# XO-Tester.net
KiCad netlist of a schematic drawn in EAGLE
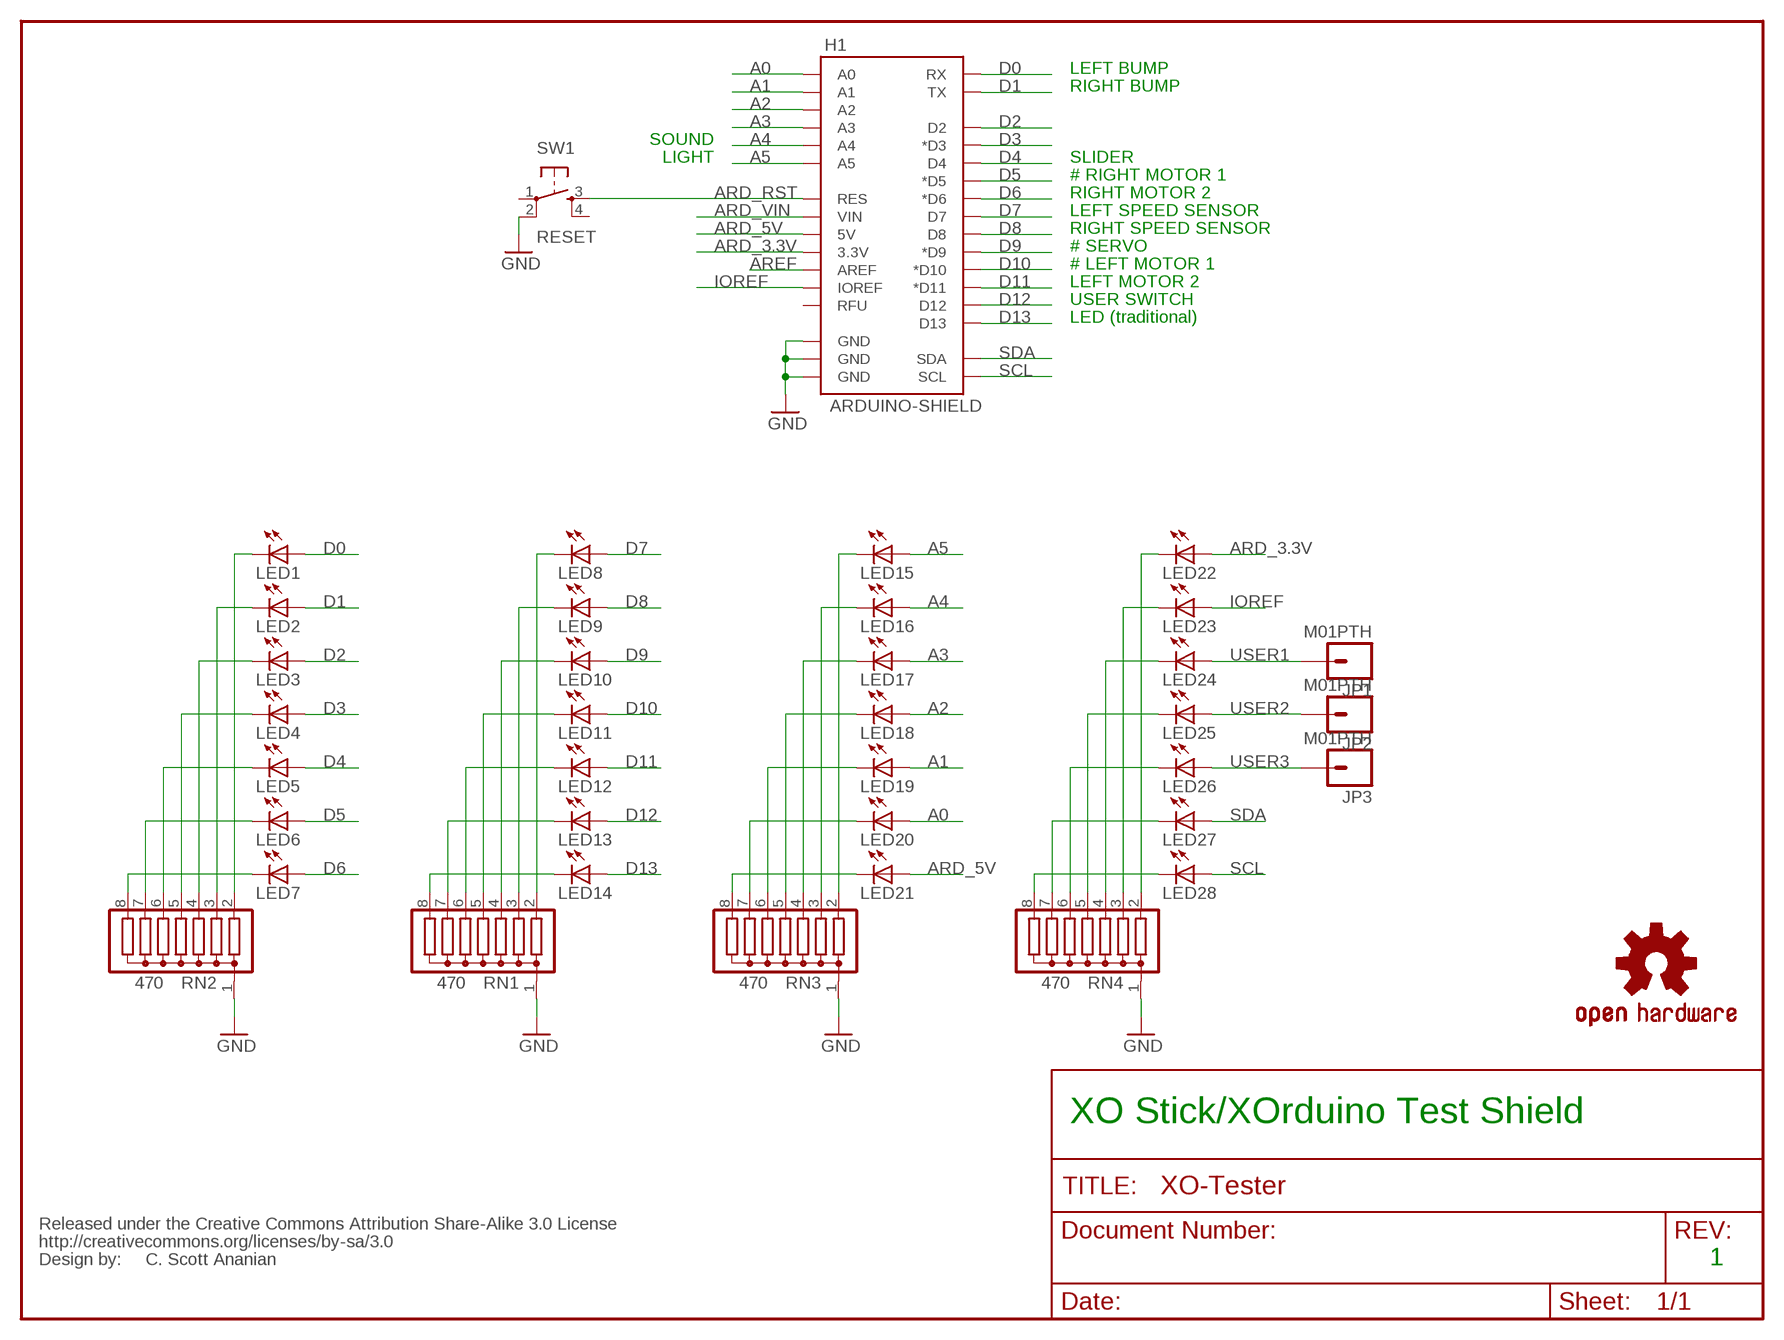
[diagram p0: schematic, sheet 1]

(export (version "E")
  (design (tool "Eeschema 10.0.6"))
  (components
    (comp (ref "H1")
      (value "ARDUINO-SHIELD")
      (footprint "eagle-import:ARDUINO-SHIELD-VIAS-HOLES")
      (libsource (lib "eagle-import") (part "ARDUINO-SHIELD"))
    )
    (comp (ref "JP1")
      (value "M01PTH")
      (footprint "eagle-import:1X01")
      (libsource (lib "eagle-import") (part "M01PTH"))
    )
    (comp (ref "JP2")
      (value "M01PTH")
      (footprint "eagle-import:1X01")
      (libsource (lib "eagle-import") (part "M01PTH"))
    )
    (comp (ref "JP3")
      (value "M01PTH")
      (footprint "eagle-import:1X01")
      (libsource (lib "eagle-import") (part "M01PTH"))
    )
    (comp (ref "LED1")
      (value "LED3MM-KIT")
      (footprint "eagle-import:LED3MM-KIT")
      (libsource (lib "eagle-import") (part "LED3MM-KIT"))
    )
    (comp (ref "LED2")
      (value "LED3MM-KIT")
      (footprint "eagle-import:LED3MM-KIT")
      (libsource (lib "eagle-import") (part "LED3MM-KIT"))
    )
    (comp (ref "LED3")
      (value "LED3MM-KIT")
      (footprint "eagle-import:LED3MM-KIT")
      (libsource (lib "eagle-import") (part "LED3MM-KIT"))
    )
    (comp (ref "LED4")
      (value "LED3MM-KIT")
      (footprint "eagle-import:LED3MM-KIT")
      (libsource (lib "eagle-import") (part "LED3MM-KIT"))
    )
    (comp (ref "LED5")
      (value "LED3MM-KIT")
      (footprint "eagle-import:LED3MM-KIT")
      (libsource (lib "eagle-import") (part "LED3MM-KIT"))
    )
    (comp (ref "LED6")
      (value "LED3MM-KIT")
      (footprint "eagle-import:LED3MM-KIT")
      (libsource (lib "eagle-import") (part "LED3MM-KIT"))
    )
    (comp (ref "LED7")
      (value "LED3MM-KIT")
      (footprint "eagle-import:LED3MM-KIT")
      (libsource (lib "eagle-import") (part "LED3MM-KIT"))
    )
    (comp (ref "LED8")
      (value "LED3MM-KIT")
      (footprint "eagle-import:LED3MM-KIT")
      (libsource (lib "eagle-import") (part "LED3MM-KIT"))
    )
    (comp (ref "LED9")
      (value "LED3MM-KIT")
      (footprint "eagle-import:LED3MM-KIT")
      (libsource (lib "eagle-import") (part "LED3MM-KIT"))
    )
    (comp (ref "LED10")
      (value "LED3MM-KIT")
      (footprint "eagle-import:LED3MM-KIT")
      (libsource (lib "eagle-import") (part "LED3MM-KIT"))
    )
    (comp (ref "LED11")
      (value "LED3MM-KIT")
      (footprint "eagle-import:LED3MM-KIT")
      (libsource (lib "eagle-import") (part "LED3MM-KIT"))
    )
    (comp (ref "LED12")
      (value "LED3MM-KIT")
      (footprint "eagle-import:LED3MM-KIT")
      (libsource (lib "eagle-import") (part "LED3MM-KIT"))
    )
    (comp (ref "LED13")
      (value "LED3MM-KIT")
      (footprint "eagle-import:LED3MM-KIT")
      (libsource (lib "eagle-import") (part "LED3MM-KIT"))
    )
    (comp (ref "LED14")
      (value "LED3MM-KIT")
      (footprint "eagle-import:LED3MM-KIT")
      (libsource (lib "eagle-import") (part "LED3MM-KIT"))
    )
    (comp (ref "LED15")
      (value "LED3MM-KIT")
      (footprint "eagle-import:LED3MM-KIT")
      (libsource (lib "eagle-import") (part "LED3MM-KIT"))
    )
    (comp (ref "LED16")
      (value "LED3MM-KIT")
      (footprint "eagle-import:LED3MM-KIT")
      (libsource (lib "eagle-import") (part "LED3MM-KIT"))
    )
    (comp (ref "LED17")
      (value "LED3MM-KIT")
      (footprint "eagle-import:LED3MM-KIT")
      (libsource (lib "eagle-import") (part "LED3MM-KIT"))
    )
    (comp (ref "LED18")
      (value "LED3MM-KIT")
      (footprint "eagle-import:LED3MM-KIT")
      (libsource (lib "eagle-import") (part "LED3MM-KIT"))
    )
    (comp (ref "LED19")
      (value "LED3MM-KIT")
      (footprint "eagle-import:LED3MM-KIT")
      (libsource (lib "eagle-import") (part "LED3MM-KIT"))
    )
    (comp (ref "LED20")
      (value "LED3MM-KIT")
      (footprint "eagle-import:LED3MM-KIT")
      (libsource (lib "eagle-import") (part "LED3MM-KIT"))
    )
    (comp (ref "LED21")
      (value "LED3MM-KIT")
      (footprint "eagle-import:LED3MM-KIT")
      (libsource (lib "eagle-import") (part "LED3MM-KIT"))
    )
    (comp (ref "LED22")
      (value "LED3MM-KIT")
      (footprint "eagle-import:LED3MM-KIT")
      (libsource (lib "eagle-import") (part "LED3MM-KIT"))
    )
    (comp (ref "LED23")
      (value "LED3MM-KIT")
      (footprint "eagle-import:LED3MM-KIT")
      (libsource (lib "eagle-import") (part "LED3MM-KIT"))
    )
    (comp (ref "LED24")
      (value "LED3MM-KIT")
      (footprint "eagle-import:LED3MM-KIT")
      (libsource (lib "eagle-import") (part "LED3MM-KIT"))
    )
    (comp (ref "LED25")
      (value "LED3MM-KIT")
      (footprint "eagle-import:LED3MM-KIT")
      (libsource (lib "eagle-import") (part "LED3MM-KIT"))
    )
    (comp (ref "LED26")
      (value "LED3MM-KIT")
      (footprint "eagle-import:LED3MM-KIT")
      (libsource (lib "eagle-import") (part "LED3MM-KIT"))
    )
    (comp (ref "LED27")
      (value "LED3MM-KIT")
      (footprint "eagle-import:LED3MM-KIT")
      (libsource (lib "eagle-import") (part "LED3MM-KIT"))
    )
    (comp (ref "LED28")
      (value "LED3MM-KIT")
      (footprint "eagle-import:LED3MM-KIT")
      (libsource (lib "eagle-import") (part "LED3MM-KIT"))
    )
    (comp (ref "RN1")
      (value "470")
      (footprint "eagle-import:SIL8")
      (libsource (lib "eagle-import") (part "G07R"))
    )
    (comp (ref "RN2")
      (value "470")
      (footprint "eagle-import:SIL8")
      (libsource (lib "eagle-import") (part "G07R"))
    )
    (comp (ref "RN3")
      (value "470")
      (footprint "eagle-import:SIL8")
      (libsource (lib "eagle-import") (part "G07R"))
    )
    (comp (ref "RN4")
      (value "470")
      (footprint "eagle-import:SIL8")
      (libsource (lib "eagle-import") (part "G07R"))
    )
    (comp (ref "SW1")
      (value "RESET")
      (footprint "eagle-import:TACTILE-PTH")
      (libsource (lib "eagle-import") (part "TAC_SWITCHPTH"))
    )
    (comp (ref "U$1")
      (value "OSHW-LOGOM")
      (footprint "eagle-import:OSHW-LOGO-M")
      (libsource (lib "eagle-import") (part "OSHW-LOGOM"))
    )
    (comp (ref "U$4")
      (value "CREATIVE_COMMONS")
      (footprint "eagle-import:CREATIVE_COMMONS")
      (libsource (lib "eagle-import") (part "CREATIVE_COMMONS"))
    )
  )
  (nets
    (net (code "1") (name "/A0") (class "Default")
      (node (ref "H1") (pin "A0") (pinfunction "A0_A0") (pintype "bidirectional"))
      (node (ref "LED20") (pin "A") (pinfunction "A_A") (pintype "passive"))
    )
    (net (code "2") (name "/A1") (class "Default")
      (node (ref "H1") (pin "A1") (pinfunction "A1_A1") (pintype "bidirectional"))
      (node (ref "LED19") (pin "A") (pinfunction "A_A") (pintype "passive"))
    )
    (net (code "3") (name "/A2") (class "Default")
      (node (ref "H1") (pin "A2") (pinfunction "A2_A2") (pintype "bidirectional"))
      (node (ref "LED18") (pin "A") (pinfunction "A_A") (pintype "passive"))
    )
    (net (code "4") (name "/A3") (class "Default")
      (node (ref "H1") (pin "A3") (pinfunction "A3_A3") (pintype "bidirectional"))
      (node (ref "LED17") (pin "A") (pinfunction "A_A") (pintype "passive"))
    )
    (net (code "5") (name "/A4") (class "Default")
      (node (ref "H1") (pin "A4") (pinfunction "A4_A4") (pintype "bidirectional"))
      (node (ref "LED16") (pin "A") (pinfunction "A_A") (pintype "passive"))
    )
    (net (code "6") (name "/A5") (class "Default")
      (node (ref "H1") (pin "A5") (pinfunction "A5_A5") (pintype "bidirectional"))
      (node (ref "LED15") (pin "A") (pinfunction "A_A") (pintype "passive"))
    )
    (net (code "7") (name "/ARD_3.3V") (class "Default")
      (node (ref "H1") (pin "3.3V") (pinfunction "3.3V_3.3V") (pintype "bidirectional"))
      (node (ref "LED22") (pin "A") (pinfunction "A_A") (pintype "passive"))
    )
    (net (code "8") (name "/ARD_5V") (class "Default")
      (node (ref "H1") (pin "5V") (pinfunction "5V_5V") (pintype "bidirectional"))
      (node (ref "LED21") (pin "A") (pinfunction "A_A") (pintype "passive"))
    )
    (net (code "9") (name "/ARD_RST") (class "Default")
      (node (ref "H1") (pin "RES") (pinfunction "RES_RES") (pintype "bidirectional"))
      (node (ref "SW1") (pin "3") (pinfunction "3_3") (pintype "passive"))
    )
    (net (code "10") (name "/ARD_VIN") (class "Default")
      (node (ref "H1") (pin "VIN") (pinfunction "VIN_VIN") (pintype "bidirectional"))
    )
    (net (code "11") (name "/AREF") (class "Default")
      (node (ref "H1") (pin "AREF") (pinfunction "AREF_AREF") (pintype "bidirectional"))
    )
    (net (code "12") (name "/D0") (class "Default")
      (node (ref "H1") (pin "RX") (pinfunction "RX_RX") (pintype "bidirectional"))
      (node (ref "LED1") (pin "A") (pinfunction "A_A") (pintype "passive"))
    )
    (net (code "13") (name "/D1") (class "Default")
      (node (ref "H1") (pin "TX") (pinfunction "TX_TX") (pintype "bidirectional"))
      (node (ref "LED2") (pin "A") (pinfunction "A_A") (pintype "passive"))
    )
    (net (code "14") (name "/D2") (class "Default")
      (node (ref "H1") (pin "D2") (pinfunction "D2_D2") (pintype "bidirectional"))
      (node (ref "LED3") (pin "A") (pinfunction "A_A") (pintype "passive"))
    )
    (net (code "15") (name "/D3") (class "Default")
      (node (ref "H1") (pin "D3") (pinfunction "*D3_D3") (pintype "bidirectional"))
      (node (ref "LED4") (pin "A") (pinfunction "A_A") (pintype "passive"))
    )
    (net (code "16") (name "/D4") (class "Default")
      (node (ref "H1") (pin "D4") (pinfunction "D4_D4") (pintype "bidirectional"))
      (node (ref "LED5") (pin "A") (pinfunction "A_A") (pintype "passive"))
    )
    (net (code "17") (name "/D5") (class "Default")
      (node (ref "H1") (pin "D5") (pinfunction "*D5_D5") (pintype "bidirectional"))
      (node (ref "LED6") (pin "A") (pinfunction "A_A") (pintype "passive"))
    )
    (net (code "18") (name "/D6") (class "Default")
      (node (ref "H1") (pin "D6") (pinfunction "*D6_D6") (pintype "bidirectional"))
      (node (ref "LED7") (pin "A") (pinfunction "A_A") (pintype "passive"))
    )
    (net (code "19") (name "/D7") (class "Default")
      (node (ref "H1") (pin "D7") (pinfunction "D7_D7") (pintype "bidirectional"))
      (node (ref "LED8") (pin "A") (pinfunction "A_A") (pintype "passive"))
    )
    (net (code "20") (name "/D8") (class "Default")
      (node (ref "H1") (pin "D8") (pinfunction "D8_D8") (pintype "bidirectional"))
      (node (ref "LED9") (pin "A") (pinfunction "A_A") (pintype "passive"))
    )
    (net (code "21") (name "/D9") (class "Default")
      (node (ref "H1") (pin "D9") (pinfunction "*D9_D9") (pintype "bidirectional"))
      (node (ref "LED10") (pin "A") (pinfunction "A_A") (pintype "passive"))
    )
    (net (code "22") (name "/D10") (class "Default")
      (node (ref "H1") (pin "D10") (pinfunction "*D10_D10") (pintype "bidirectional"))
      (node (ref "LED11") (pin "A") (pinfunction "A_A") (pintype "passive"))
    )
    (net (code "23") (name "/D11") (class "Default")
      (node (ref "H1") (pin "D11") (pinfunction "*D11_D11") (pintype "bidirectional"))
      (node (ref "LED12") (pin "A") (pinfunction "A_A") (pintype "passive"))
    )
    (net (code "24") (name "/D12") (class "Default")
      (node (ref "H1") (pin "D12") (pinfunction "D12_D12") (pintype "bidirectional"))
      (node (ref "LED13") (pin "A") (pinfunction "A_A") (pintype "passive"))
    )
    (net (code "25") (name "/D13") (class "Default")
      (node (ref "H1") (pin "D13") (pinfunction "D13_D13") (pintype "bidirectional"))
      (node (ref "LED14") (pin "A") (pinfunction "A_A") (pintype "passive"))
    )
    (net (code "26") (name "/IOREF") (class "Default")
      (node (ref "H1") (pin "IOREF") (pinfunction "IOREF_IOREF") (pintype "bidirectional"))
      (node (ref "LED23") (pin "A") (pinfunction "A_A") (pintype "passive"))
    )
    (net (code "27") (name "/SCL") (class "Default")
      (node (ref "H1") (pin "SCL") (pinfunction "SCL_SCL") (pintype "bidirectional"))
      (node (ref "LED28") (pin "A") (pinfunction "A_A") (pintype "passive"))
    )
    (net (code "28") (name "/SDA") (class "Default")
      (node (ref "H1") (pin "SDA") (pinfunction "SDA_SDA") (pintype "bidirectional"))
      (node (ref "LED27") (pin "A") (pinfunction "A_A") (pintype "passive"))
    )
    (net (code "29") (name "/USER1") (class "Default")
      (node (ref "JP1") (pin "1") (pinfunction "1_1") (pintype "passive"))
      (node (ref "LED24") (pin "A") (pinfunction "A_A") (pintype "passive"))
    )
    (net (code "30") (name "/USER2") (class "Default")
      (node (ref "JP2") (pin "1") (pinfunction "1_1") (pintype "passive"))
      (node (ref "LED25") (pin "A") (pinfunction "A_A") (pintype "passive"))
    )
    (net (code "31") (name "/USER3") (class "Default")
      (node (ref "JP3") (pin "1") (pinfunction "1_1") (pintype "passive"))
      (node (ref "LED26") (pin "A") (pinfunction "A_A") (pintype "passive"))
    )
    (net (code "32") (name "GND") (class "Default")
      (node (ref "H1") (pin "GND@0") (pinfunction "GND_GND@0") (pintype "bidirectional"))
      (node (ref "H1") (pin "GND@1") (pinfunction "GND_GND@1") (pintype "bidirectional"))
      (node (ref "H1") (pin "GND@2") (pinfunction "GND_GND@2") (pintype "bidirectional"))
      (node (ref "RN1") (pin "1") (pinfunction "1_1") (pintype "passive"))
      (node (ref "RN2") (pin "1") (pinfunction "1_1") (pintype "passive"))
      (node (ref "RN3") (pin "1") (pinfunction "1_1") (pintype "passive"))
      (node (ref "RN4") (pin "1") (pinfunction "1_1") (pintype "passive"))
      (node (ref "SW1") (pin "2") (pinfunction "2_2") (pintype "passive"))
    )
    (net (code "33") (name "Net-(LED1-C)") (class "Default")
      (node (ref "LED1") (pin "K") (pinfunction "C_K") (pintype "passive"))
      (node (ref "RN2") (pin "2") (pinfunction "2_2") (pintype "passive"))
    )
    (net (code "34") (name "Net-(LED2-C)") (class "Default")
      (node (ref "LED2") (pin "K") (pinfunction "C_K") (pintype "passive"))
      (node (ref "RN2") (pin "3") (pinfunction "3_3") (pintype "passive"))
    )
    (net (code "35") (name "Net-(LED3-C)") (class "Default")
      (node (ref "LED3") (pin "K") (pinfunction "C_K") (pintype "passive"))
      (node (ref "RN2") (pin "4") (pinfunction "4_4") (pintype "passive"))
    )
    (net (code "36") (name "Net-(LED4-C)") (class "Default")
      (node (ref "LED4") (pin "K") (pinfunction "C_K") (pintype "passive"))
      (node (ref "RN2") (pin "5") (pinfunction "5_5") (pintype "passive"))
    )
    (net (code "37") (name "Net-(LED5-C)") (class "Default")
      (node (ref "LED5") (pin "K") (pinfunction "C_K") (pintype "passive"))
      (node (ref "RN2") (pin "6") (pinfunction "6_6") (pintype "passive"))
    )
    (net (code "38") (name "Net-(LED6-C)") (class "Default")
      (node (ref "LED6") (pin "K") (pinfunction "C_K") (pintype "passive"))
      (node (ref "RN2") (pin "7") (pinfunction "7_7") (pintype "passive"))
    )
    (net (code "39") (name "Net-(LED7-C)") (class "Default")
      (node (ref "LED7") (pin "K") (pinfunction "C_K") (pintype "passive"))
      (node (ref "RN2") (pin "8") (pinfunction "8_8") (pintype "passive"))
    )
    (net (code "40") (name "Net-(LED8-C)") (class "Default")
      (node (ref "LED8") (pin "K") (pinfunction "C_K") (pintype "passive"))
      (node (ref "RN1") (pin "2") (pinfunction "2_2") (pintype "passive"))
    )
    (net (code "41") (name "Net-(LED9-C)") (class "Default")
      (node (ref "LED9") (pin "K") (pinfunction "C_K") (pintype "passive"))
      (node (ref "RN1") (pin "3") (pinfunction "3_3") (pintype "passive"))
    )
    (net (code "42") (name "Net-(LED10-C)") (class "Default")
      (node (ref "LED10") (pin "K") (pinfunction "C_K") (pintype "passive"))
      (node (ref "RN1") (pin "4") (pinfunction "4_4") (pintype "passive"))
    )
    (net (code "43") (name "Net-(LED11-C)") (class "Default")
      (node (ref "LED11") (pin "K") (pinfunction "C_K") (pintype "passive"))
      (node (ref "RN1") (pin "5") (pinfunction "5_5") (pintype "passive"))
    )
    (net (code "44") (name "Net-(LED12-C)") (class "Default")
      (node (ref "LED12") (pin "K") (pinfunction "C_K") (pintype "passive"))
      (node (ref "RN1") (pin "6") (pinfunction "6_6") (pintype "passive"))
    )
    (net (code "45") (name "Net-(LED13-C)") (class "Default")
      (node (ref "LED13") (pin "K") (pinfunction "C_K") (pintype "passive"))
      (node (ref "RN1") (pin "7") (pinfunction "7_7") (pintype "passive"))
    )
    (net (code "46") (name "Net-(LED14-C)") (class "Default")
      (node (ref "LED14") (pin "K") (pinfunction "C_K") (pintype "passive"))
      (node (ref "RN1") (pin "8") (pinfunction "8_8") (pintype "passive"))
    )
    (net (code "47") (name "Net-(LED15-C)") (class "Default")
      (node (ref "LED15") (pin "K") (pinfunction "C_K") (pintype "passive"))
      (node (ref "RN3") (pin "2") (pinfunction "2_2") (pintype "passive"))
    )
    (net (code "48") (name "Net-(LED16-C)") (class "Default")
      (node (ref "LED16") (pin "K") (pinfunction "C_K") (pintype "passive"))
      (node (ref "RN3") (pin "3") (pinfunction "3_3") (pintype "passive"))
    )
    (net (code "49") (name "Net-(LED17-C)") (class "Default")
      (node (ref "LED17") (pin "K") (pinfunction "C_K") (pintype "passive"))
      (node (ref "RN3") (pin "4") (pinfunction "4_4") (pintype "passive"))
    )
    (net (code "50") (name "Net-(LED18-C)") (class "Default")
      (node (ref "LED18") (pin "K") (pinfunction "C_K") (pintype "passive"))
      (node (ref "RN3") (pin "5") (pinfunction "5_5") (pintype "passive"))
    )
    (net (code "51") (name "Net-(LED19-C)") (class "Default")
      (node (ref "LED19") (pin "K") (pinfunction "C_K") (pintype "passive"))
      (node (ref "RN3") (pin "6") (pinfunction "6_6") (pintype "passive"))
    )
    (net (code "52") (name "Net-(LED20-C)") (class "Default")
      (node (ref "LED20") (pin "K") (pinfunction "C_K") (pintype "passive"))
      (node (ref "RN3") (pin "7") (pinfunction "7_7") (pintype "passive"))
    )
    (net (code "53") (name "Net-(LED21-C)") (class "Default")
      (node (ref "LED21") (pin "K") (pinfunction "C_K") (pintype "passive"))
      (node (ref "RN3") (pin "8") (pinfunction "8_8") (pintype "passive"))
    )
    (net (code "54") (name "Net-(LED22-C)") (class "Default")
      (node (ref "LED22") (pin "K") (pinfunction "C_K") (pintype "passive"))
      (node (ref "RN4") (pin "2") (pinfunction "2_2") (pintype "passive"))
    )
    (net (code "55") (name "Net-(LED23-C)") (class "Default")
      (node (ref "LED23") (pin "K") (pinfunction "C_K") (pintype "passive"))
      (node (ref "RN4") (pin "3") (pinfunction "3_3") (pintype "passive"))
    )
    (net (code "56") (name "Net-(LED24-C)") (class "Default")
      (node (ref "LED24") (pin "K") (pinfunction "C_K") (pintype "passive"))
      (node (ref "RN4") (pin "4") (pinfunction "4_4") (pintype "passive"))
    )
    (net (code "57") (name "Net-(LED25-C)") (class "Default")
      (node (ref "LED25") (pin "K") (pinfunction "C_K") (pintype "passive"))
      (node (ref "RN4") (pin "5") (pinfunction "5_5") (pintype "passive"))
    )
    (net (code "58") (name "Net-(LED26-C)") (class "Default")
      (node (ref "LED26") (pin "K") (pinfunction "C_K") (pintype "passive"))
      (node (ref "RN4") (pin "6") (pinfunction "6_6") (pintype "passive"))
    )
    (net (code "59") (name "Net-(LED27-C)") (class "Default")
      (node (ref "LED27") (pin "K") (pinfunction "C_K") (pintype "passive"))
      (node (ref "RN4") (pin "7") (pinfunction "7_7") (pintype "passive"))
    )
    (net (code "60") (name "Net-(LED28-C)") (class "Default")
      (node (ref "LED28") (pin "K") (pinfunction "C_K") (pintype "passive"))
      (node (ref "RN4") (pin "8") (pinfunction "8_8") (pintype "passive"))
    )
    (net (code "61") (name "unconnected-(H1-PadRFU)") (class "Default")
      (node (ref "H1") (pin "RFU") (pinfunction "RFU_RFU") (pintype "bidirectional"))
    )
    (net (code "62") (name "unconnected-(SW1-Pad1)") (class "Default")
      (node (ref "SW1") (pin "1") (pinfunction "1_1") (pintype "passive"))
    )
    (net (code "63") (name "unconnected-(SW1-Pad4)") (class "Default")
      (node (ref "SW1") (pin "4") (pinfunction "4_4") (pintype "passive"))
    )
  )
)
